# RS485.net
KiCad netlist of a schematic drawn in Altium Designer
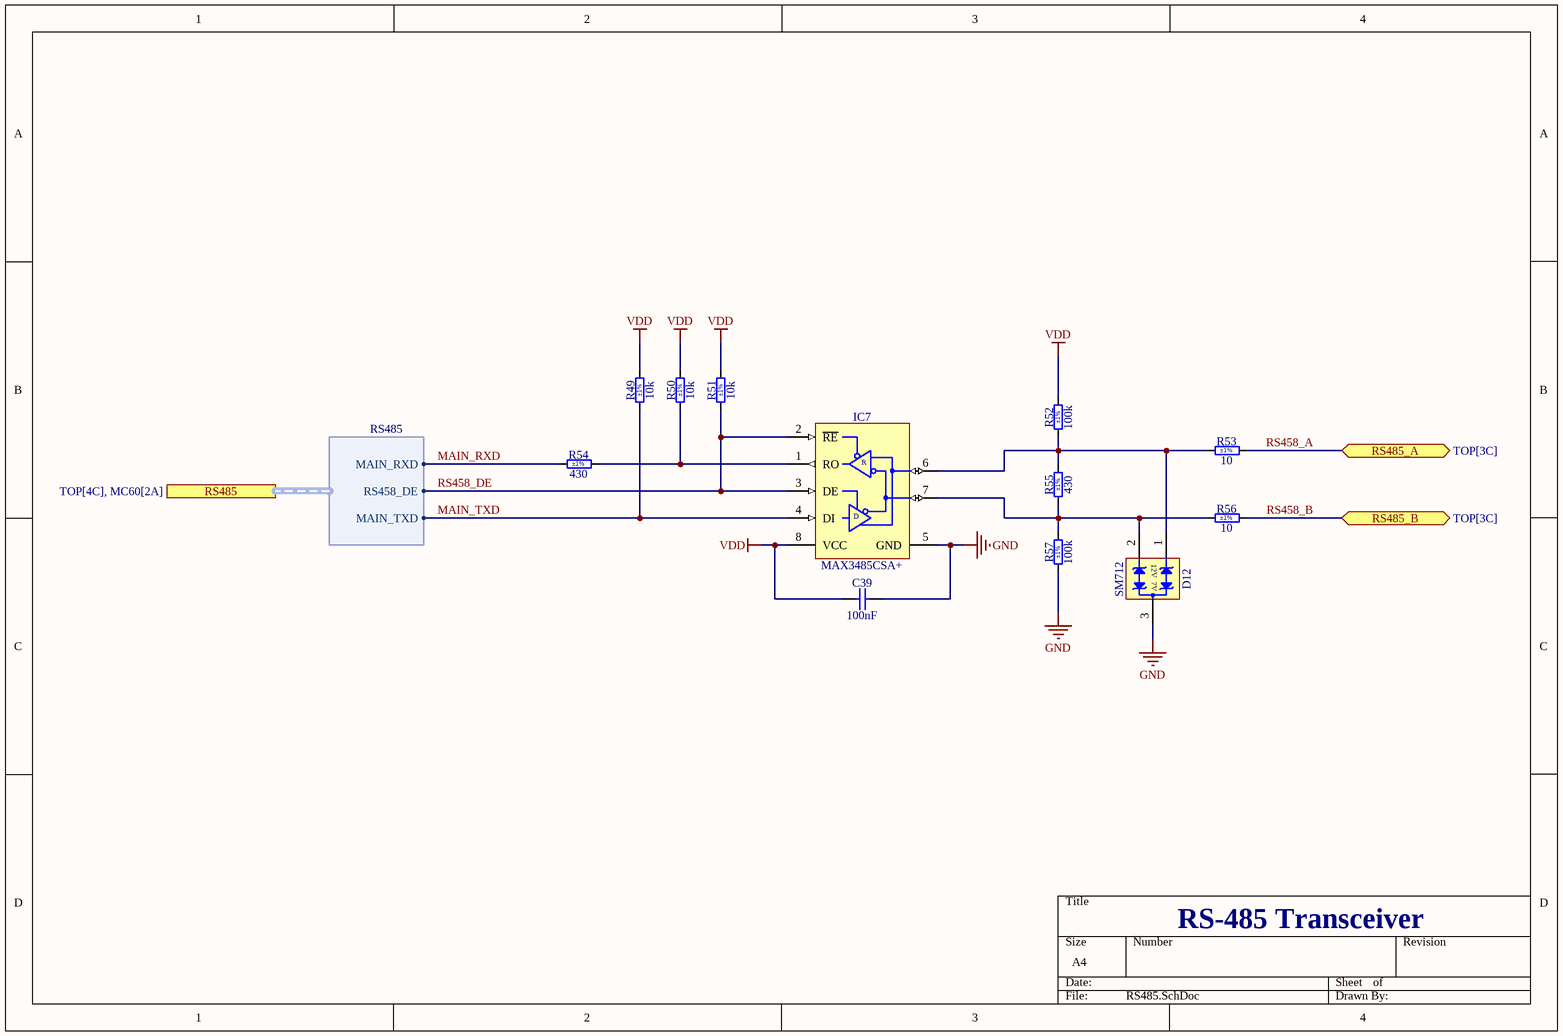
[diagram p0: RS485.SchDoc]

(export (version "E")
  (design (tool "Eeschema 10.0.6"))
  (components
    (comp (ref "C39")
      (value "100nF")
      (footprint "CAPC1608X87N")
      (description "Non-polarised capacitor")
      (fields
        (field (name "PART NUMBER") "CC0603_100NF_50V_10%_X7R")
        (field (name "VOLTAGE") "50V")
        (field (name "AUTHOR") "CERN DEM JLC")
      )
      (libsource (lib "Capacitors") (part "Capacitor - non polarized"))
    )
    (comp (ref "D12")
      (value "SM712")
      (footprint "SOT95P237X112-3N")
      (description "Asymmetrical TVS Diode for Extended Common-Mode RS-485")
      (fields
        (field (name "VOLTAGE") "12V/-7V")
        (field (name "POWER") "400W")
        (field (name "AUTHOR") "CERN DEM JLC")
      )
      (libsource (lib "ICs And Semiconductors") (part "SM712"))
    )
    (comp (ref "IC7")
      (value "MAX3485CSA+")
      (footprint "SOIC127P600X175-8N")
      (description "3.3V-Powered, ±15kV ESD-Protected, 10Mbps,True RS-485/RS-422 Half Duplex Transceiver")
      (fields (field (name "MANUFACTURER") "MAXIM") (field (name "AUTHOR") "CERN DEM JLC"))
      (libsource (lib "ICs And Semiconductors") (part "MAX3485"))
    )
    (comp (ref "R49")
      (value "10k")
      (footprint "RESC1608X55N")
      (description "Resistor - 1%")
      (fields
        (field (name "TOLERANCE") "±1%")
        (field (name "PART NUMBER") "R0603_10K_1%_0.1W_100PPM")
        (field (name "POWER") "0.1W")
        (field (name "AUTHOR") "CERN DEM JLC")
      )
      (libsource (lib "Resistors") (part "Resistor - 1%"))
    )
    (comp (ref "R50")
      (value "10k")
      (footprint "RESC1608X55N")
      (description "Resistor - 1%")
      (fields
        (field (name "TOLERANCE") "±1%")
        (field (name "PART NUMBER") "R0603_10K_1%_0.1W_100PPM")
        (field (name "POWER") "0.1W")
        (field (name "AUTHOR") "CERN DEM JLC")
      )
      (libsource (lib "Resistors") (part "Resistor - 1%"))
    )
    (comp (ref "R51")
      (value "10k")
      (footprint "RESC1608X55N")
      (description "Resistor - 1%")
      (fields
        (field (name "TOLERANCE") "±1%")
        (field (name "PART NUMBER") "R0603_10K_1%_0.1W_100PPM")
        (field (name "POWER") "0.1W")
        (field (name "AUTHOR") "CERN DEM JLC")
      )
      (libsource (lib "Resistors") (part "Resistor - 1%"))
    )
    (comp (ref "R52")
      (value "100k")
      (footprint "RESC1608X55N")
      (description "Resistor - 1%")
      (fields
        (field (name "TOLERANCE") "±1%")
        (field (name "PART NUMBER") "R0603_100K_1%_0.1W_100PPM")
        (field (name "POWER") "0.1W")
        (field (name "AUTHOR") "CERN DEM JLC")
      )
      (libsource (lib "Resistors") (part "Resistor - 1%"))
    )
    (comp (ref "R53")
      (value "10")
      (footprint "RESC1608X55N")
      (description "Resistor - 1%")
      (fields
        (field (name "TOLERANCE") "±1%")
        (field (name "PART NUMBER") "R0603_10R_1%_0.1W_200PPM")
        (field (name "POWER") "0.1W")
        (field (name "AUTHOR") "CERN DEM JLC")
      )
      (libsource (lib "Resistors") (part "Resistor - 1%"))
    )
    (comp (ref "R54")
      (value "430")
      (footprint "RESC1608X55N")
      (description "Resistor - 1%")
      (fields
        (field (name "TOLERANCE") "±1%")
        (field (name "PART NUMBER") "R0603_430R_1%_0.1W_100PPM")
        (field (name "POWER") "0.1W")
        (field (name "AUTHOR") "CERN DEM JLC")
      )
      (libsource (lib "Resistors") (part "Resistor - 1%"))
    )
    (comp (ref "R55")
      (value "430")
      (footprint "RESC1608X55N")
      (description "Resistor - 1%")
      (fields
        (field (name "TOLERANCE") "±1%")
        (field (name "PART NUMBER") "R0603_430R_1%_0.1W_100PPM")
        (field (name "POWER") "0.1W")
        (field (name "AUTHOR") "CERN DEM JLC")
      )
      (libsource (lib "Resistors") (part "Resistor - 1%"))
    )
    (comp (ref "R56")
      (value "10")
      (footprint "RESC1608X55N")
      (description "Resistor - 1%")
      (fields
        (field (name "TOLERANCE") "±1%")
        (field (name "PART NUMBER") "R0603_10R_1%_0.1W_200PPM")
        (field (name "POWER") "0.1W")
        (field (name "AUTHOR") "CERN DEM JLC")
      )
      (libsource (lib "Resistors") (part "Resistor - 1%"))
    )
    (comp (ref "R57")
      (value "100k")
      (footprint "RESC1608X55N")
      (description "Resistor - 1%")
      (fields
        (field (name "TOLERANCE") "±1%")
        (field (name "PART NUMBER") "R0603_100K_1%_0.1W_100PPM")
        (field (name "POWER") "0.1W")
        (field (name "AUTHOR") "CERN DEM JLC")
      )
      (libsource (lib "Resistors") (part "Resistor - 1%"))
    )
  )
  (nets
    (net (code "2") (name "/MAIN_RXD") (class "Default")
      (node (ref "R54") (pin "1") (pinfunction "1_1") (pintype "passive"))
    )
    (net (code "3") (name "/MAIN_TXD") (class "Default")
      (node (ref "IC7") (pin "4") (pinfunction "DI_4") (pintype "input"))
      (node (ref "R49") (pin "1") (pinfunction "1_1") (pintype "passive"))
    )
    (net (code "4") (name "/RS458_A") (class "Default")
      (node (ref "R53") (pin "2") (pinfunction "2_2") (pintype "passive"))
    )
    (net (code "5") (name "/RS458_B") (class "Default")
      (node (ref "R56") (pin "2") (pinfunction "2_2") (pintype "passive"))
    )
    (net (code "6") (name "/RS458_DE") (class "Default")
      (node (ref "IC7") (pin "2") (pinfunction "~{RE}_2") (pintype "input"))
      (node (ref "IC7") (pin "3") (pinfunction "DE_3") (pintype "input"))
      (node (ref "R51") (pin "1") (pinfunction "1_1") (pintype "passive"))
    )
    (net (code "8") (name "GND") (class "Default")
      (node (ref "C39") (pin "2") (pinfunction "2_2") (pintype "passive"))
      (node (ref "D12") (pin "3") (pinfunction "GND_3") (pintype "passive"))
      (node (ref "IC7") (pin "5") (pinfunction "GND_5") (pintype "power_in"))
      (node (ref "R57") (pin "1") (pinfunction "1_1") (pintype "passive"))
    )
    (net (code "9") (name "Net-(D12-I{slash}O1)") (class "Default")
      (node (ref "D12") (pin "1") (pinfunction "I/O1_1") (pintype "passive"))
      (node (ref "IC7") (pin "6") (pinfunction "A_6") (pintype "bidirectional"))
      (node (ref "R52") (pin "1") (pinfunction "1_1") (pintype "passive"))
      (node (ref "R53") (pin "1") (pinfunction "1_1") (pintype "passive"))
      (node (ref "R55") (pin "2") (pinfunction "2_2") (pintype "passive"))
    )
    (net (code "10") (name "Net-(D12-I{slash}O2)") (class "Default")
      (node (ref "D12") (pin "2") (pinfunction "I/O2_2") (pintype "passive"))
      (node (ref "IC7") (pin "7") (pinfunction "B_7") (pintype "bidirectional"))
      (node (ref "R55") (pin "1") (pinfunction "1_1") (pintype "passive"))
      (node (ref "R56") (pin "1") (pinfunction "1_1") (pintype "passive"))
      (node (ref "R57") (pin "2") (pinfunction "2_2") (pintype "passive"))
    )
    (net (code "11") (name "Net-(IC7-RO)") (class "Default")
      (node (ref "IC7") (pin "1") (pinfunction "RO_1") (pintype "output"))
      (node (ref "R50") (pin "1") (pinfunction "1_1") (pintype "passive"))
      (node (ref "R54") (pin "2") (pinfunction "2_2") (pintype "passive"))
    )
    (net (code "12") (name "VDD") (class "Default")
      (node (ref "C39") (pin "1") (pinfunction "1_1") (pintype "passive"))
      (node (ref "IC7") (pin "8") (pinfunction "VCC_8") (pintype "power_in"))
      (node (ref "R49") (pin "2") (pinfunction "2_2") (pintype "passive"))
      (node (ref "R50") (pin "2") (pinfunction "2_2") (pintype "passive"))
      (node (ref "R51") (pin "2") (pinfunction "2_2") (pintype "passive"))
      (node (ref "R52") (pin "2") (pinfunction "2_2") (pintype "passive"))
    )
  )
)
